# UV_Controller.net
KiCad netlist of a schematic drawn in EAGLE
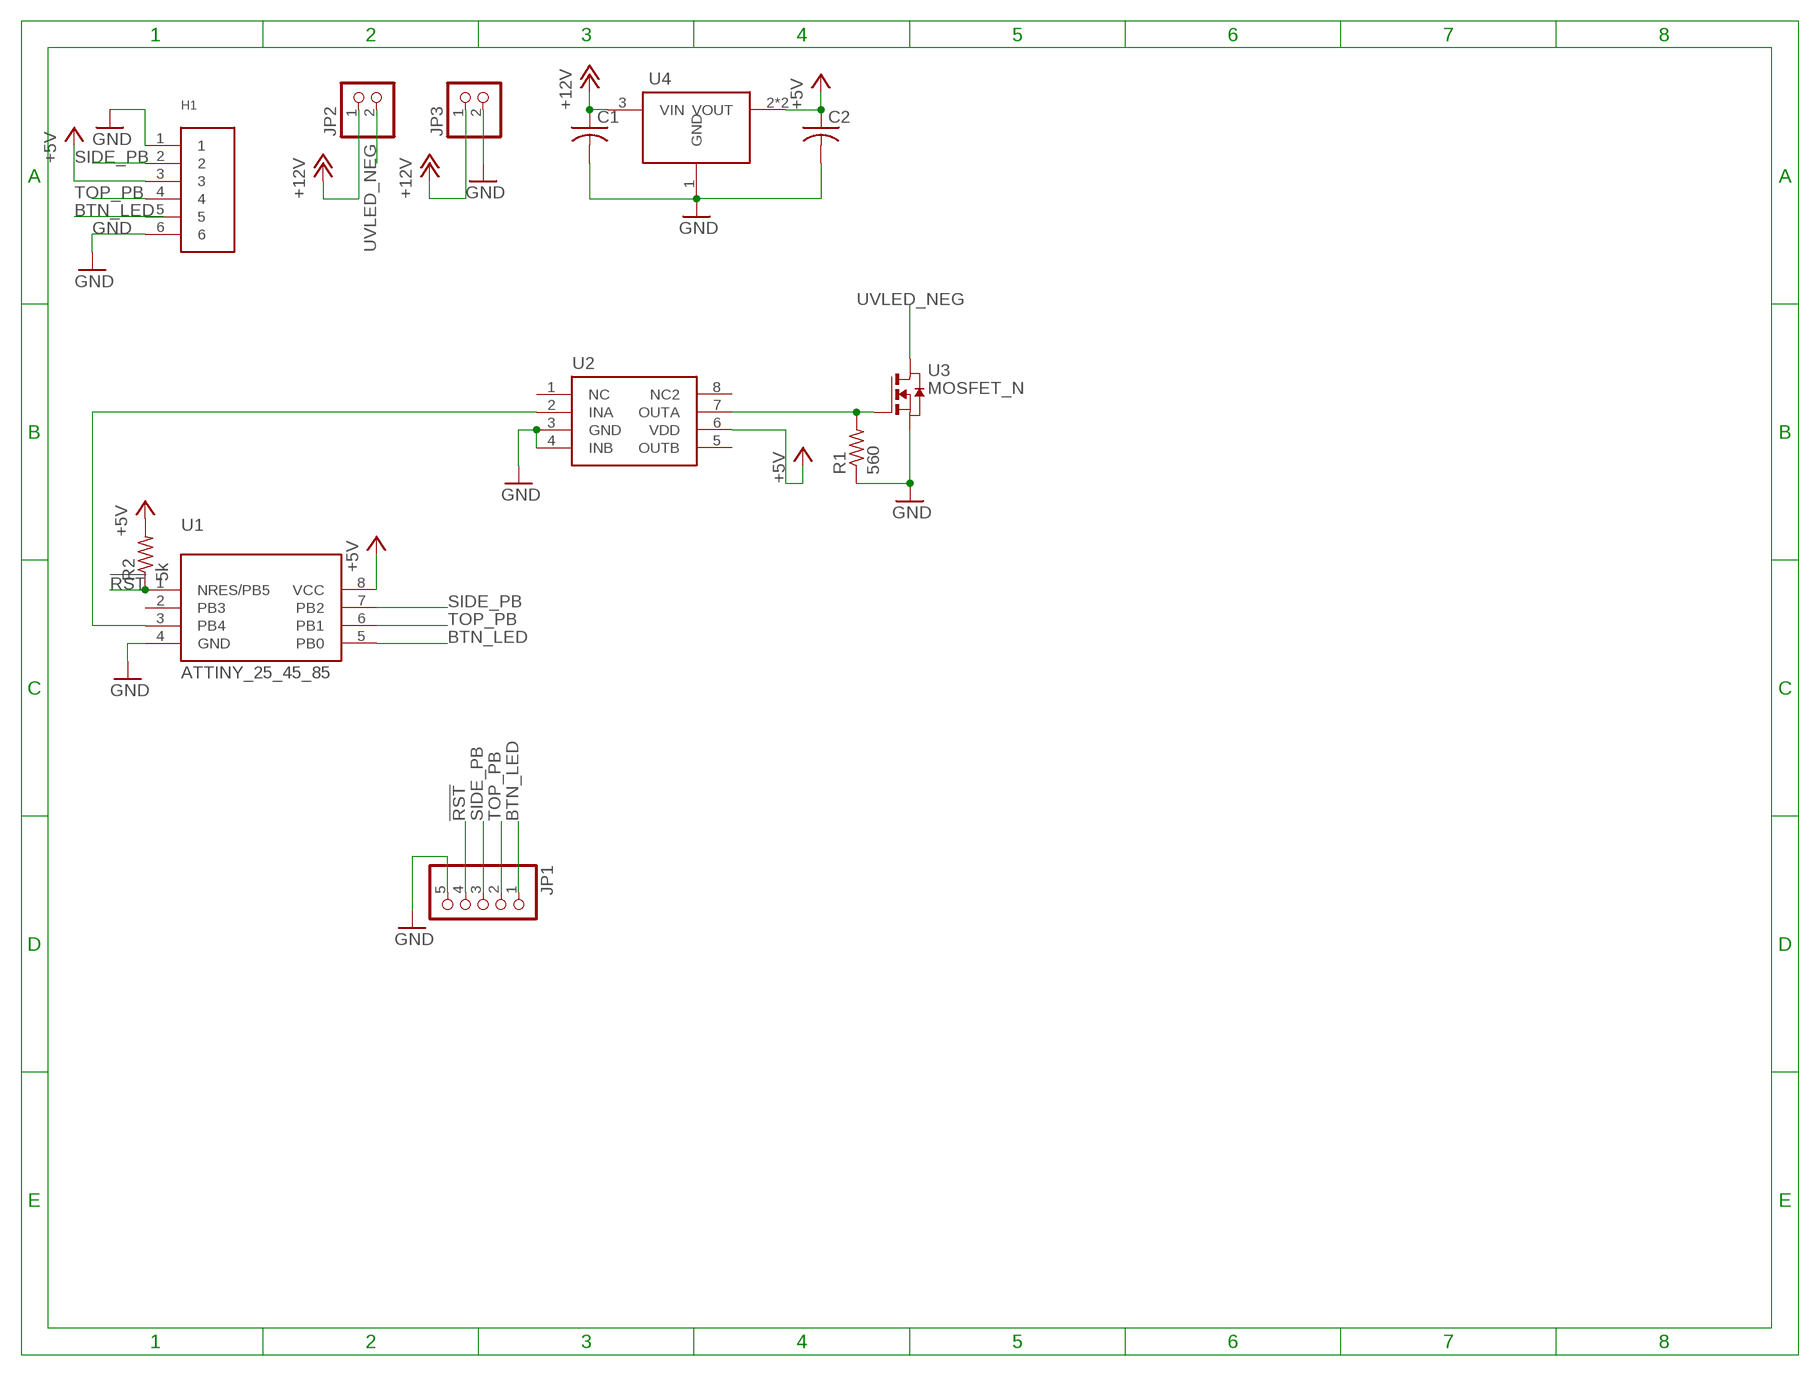
[diagram p0: schematic, sheet 1]

(export (version "E")
  (design (tool "Eeschema 10.0.6"))
  (components
    (comp (ref "C1")
      (value "C-USC0805")
      (footprint "eagle-import:C0805")
      (libsource (lib "eagle-import") (part "C-USC0805"))
    )
    (comp (ref "C2")
      (value "C-USC0805")
      (footprint "eagle-import:C0805")
      (libsource (lib "eagle-import") (part "C-USC0805"))
    )
    (comp (ref "H1")
      (value "6PIN_RIBBON_CONN_1MM")
      (footprint "eagle-import:6PIN_SMD_CONN_1MM")
      (libsource (lib "eagle-import") (part "6PIN_RIBBON_CONN_1MM"))
    )
    (comp (ref "JP1")
      (value "PINHD-1X5")
      (footprint "eagle-import:1X05")
      (libsource (lib "eagle-import") (part "PINHD-1X5"))
    )
    (comp (ref "JP2")
      (value "PINHD-1X2")
      (footprint "eagle-import:1X02")
      (libsource (lib "eagle-import") (part "PINHD-1X2"))
    )
    (comp (ref "JP3")
      (value "PINHD-1X2")
      (footprint "eagle-import:1X02")
      (libsource (lib "eagle-import") (part "PINHD-1X2"))
    )
    (comp (ref "R1")
      (value "560")
      (footprint "eagle-import:R0805")
      (libsource (lib "eagle-import") (part "R-US_R0805"))
    )
    (comp (ref "R2")
      (value "5k")
      (footprint "eagle-import:R0805")
      (libsource (lib "eagle-import") (part "R-US_R0805"))
    )
    (comp (ref "U1")
      (value "ATTINY_25_45_85")
      (footprint "eagle-import:SOIC-8")
      (libsource (lib "eagle-import") (part "ATTINY_25_45_85"))
    )
    (comp (ref "U2")
      (value "TC427")
      (footprint "eagle-import:SOIC-8")
      (libsource (lib "eagle-import") (part "TC427"))
    )
    (comp (ref "U3")
      (value "MOSFET_N")
      (footprint "eagle-import:SOT-23")
      (libsource (lib "eagle-import") (part "MOSFET_N"))
    )
    (comp (ref "U4")
      (value "NCP1117ST50T3G")
      (footprint "eagle-import:SOT223")
      (libsource (lib "eagle-import") (part "NCP1117ST50T3G"))
    )
  )
  (nets
    (net (code "1") (name "+5V") (class "Default")
      (node (ref "C2") (pin "1") (pinfunction "1_1") (pintype "passive"))
      (node (ref "H1") (pin "3") (pinfunction "3_3") (pintype "bidirectional"))
      (node (ref "R2") (pin "2") (pinfunction "2_2") (pintype "passive"))
      (node (ref "U1") (pin "8") (pinfunction "VCC_8") (pintype "power_in"))
      (node (ref "U2") (pin "6") (pinfunction "VDD_6") (pintype "bidirectional"))
      (node (ref "U4") (pin "2") (pinfunction "VOUT_2") (pintype "bidirectional"))
      (node (ref "U4") (pin "4") (pinfunction "VOUT_4") (pintype "bidirectional"))
    )
    (net (code "2") (name "+12V") (class "Default")
      (node (ref "C1") (pin "1") (pinfunction "1_1") (pintype "passive"))
      (node (ref "JP2") (pin "1") (pinfunction "1_1") (pintype "passive"))
      (node (ref "JP3") (pin "1") (pinfunction "1_1") (pintype "passive"))
      (node (ref "U4") (pin "3") (pinfunction "VIN_3") (pintype "bidirectional"))
    )
    (net (code "3") (name "/BTN_LED") (class "Default")
      (node (ref "H1") (pin "5") (pinfunction "5_5") (pintype "bidirectional"))
      (node (ref "JP1") (pin "1") (pinfunction "1_1") (pintype "passive"))
      (node (ref "U1") (pin "5") (pinfunction "PB0_5") (pintype "bidirectional"))
    )
    (net (code "4") (name "/SIDE_PB") (class "Default")
      (node (ref "H1") (pin "2") (pinfunction "2_2") (pintype "bidirectional"))
      (node (ref "JP1") (pin "3") (pinfunction "3_3") (pintype "passive"))
      (node (ref "U1") (pin "7") (pinfunction "PB2_7") (pintype "bidirectional"))
    )
    (net (code "5") (name "/TOP_PB") (class "Default")
      (node (ref "H1") (pin "4") (pinfunction "4_4") (pintype "bidirectional"))
      (node (ref "JP1") (pin "2") (pinfunction "2_2") (pintype "passive"))
      (node (ref "U1") (pin "6") (pinfunction "PB1_6") (pintype "bidirectional"))
    )
    (net (code "6") (name "/UVLED_NEG") (class "Default")
      (node (ref "JP2") (pin "2") (pinfunction "2_2") (pintype "passive"))
      (node (ref "U3") (pin "1") (pinfunction "D_1") (pintype "passive"))
    )
    (net (code "7") (name "/~{RST}") (class "Default")
      (node (ref "JP1") (pin "4") (pinfunction "4_4") (pintype "passive"))
      (node (ref "R2") (pin "1") (pinfunction "1_1") (pintype "passive"))
      (node (ref "U1") (pin "1") (pinfunction "NRES/PB5_1") (pintype "bidirectional"))
    )
    (net (code "8") (name "GND") (class "Default")
      (node (ref "C1") (pin "2") (pinfunction "2_2") (pintype "passive"))
      (node (ref "C2") (pin "2") (pinfunction "2_2") (pintype "passive"))
      (node (ref "H1") (pin "1") (pinfunction "1_1") (pintype "bidirectional"))
      (node (ref "H1") (pin "6") (pinfunction "6_6") (pintype "bidirectional"))
      (node (ref "JP1") (pin "5") (pinfunction "5_5") (pintype "passive"))
      (node (ref "JP3") (pin "2") (pinfunction "2_2") (pintype "passive"))
      (node (ref "R1") (pin "1") (pinfunction "1_1") (pintype "passive"))
      (node (ref "U1") (pin "4") (pinfunction "GND_4") (pintype "power_in"))
      (node (ref "U2") (pin "3") (pinfunction "GND_3") (pintype "bidirectional"))
      (node (ref "U2") (pin "4") (pinfunction "INB_4") (pintype "bidirectional"))
      (node (ref "U3") (pin "3") (pinfunction "S_3") (pintype "passive"))
      (node (ref "U4") (pin "1") (pinfunction "GND_1") (pintype "bidirectional"))
    )
    (net (code "9") (name "Net-(U1-PB4)") (class "Default")
      (node (ref "U1") (pin "3") (pinfunction "PB4_3") (pintype "bidirectional"))
      (node (ref "U2") (pin "2") (pinfunction "INA_2") (pintype "bidirectional"))
    )
    (net (code "10") (name "Net-(U2-OUTA)") (class "Default")
      (node (ref "R1") (pin "2") (pinfunction "2_2") (pintype "passive"))
      (node (ref "U2") (pin "7") (pinfunction "OUTA_7") (pintype "bidirectional"))
      (node (ref "U3") (pin "2") (pinfunction "G_2") (pintype "passive"))
    )
    (net (code "11") (name "unconnected-(U1-PB3-Pad2)") (class "Default")
      (node (ref "U1") (pin "2") (pinfunction "PB3_2") (pintype "bidirectional"))
    )
    (net (code "12") (name "unconnected-(U2-NC-Pad1)") (class "Default")
      (node (ref "U2") (pin "1") (pinfunction "NC_1") (pintype "bidirectional"))
    )
    (net (code "13") (name "unconnected-(U2-NC2-Pad8)") (class "Default")
      (node (ref "U2") (pin "8") (pinfunction "NC2_8") (pintype "bidirectional"))
    )
    (net (code "14") (name "unconnected-(U2-OUTB-Pad5)") (class "Default")
      (node (ref "U2") (pin "5") (pinfunction "OUTB_5") (pintype "bidirectional"))
    )
  )
)
